# Power.net
KiCad netlist of a schematic drawn in Altium Designer
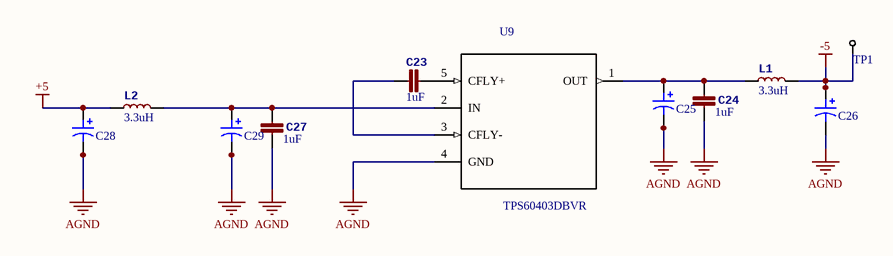
[diagram p0: Power.SchDoc]

(export (version "E")
  (design (tool "Eeschema 10.0.6"))
  (components
    (comp (ref "C23")
      (value "1uF")
      (footprint "_0805")
      (fields (field (name "Comment") "Cap"))
      (libsource (lib "") (part "Cap_1_1"))
    )
    (comp (ref "C24")
      (value "1uF")
      (footprint "_0805")
      (fields (field (name "Comment") "Cap"))
      (libsource (lib "Passives_Integrated_Library") (part "Cap_1"))
    )
    (comp (ref "C25")
      (value "100uF50V")
      (footprint "Cap electrolitic radial 10x20-5")
      (description "Cap electrolitic radial")
      (fields (field (name "DESIGNER") "Abbas Basereh"))
      (libsource (lib "Passives_Integrated_Library") (part "Cap ELECTROLITIC TOTAL SIZE"))
    )
    (comp (ref "C26")
      (value "100uF50V")
      (footprint "Cap electrolitic radial 10x20-5")
      (description "Cap electrolitic radial")
      (fields (field (name "DESIGNER") "Abbas Basereh"))
      (libsource (lib "Passives_Integrated_Library") (part "Cap ELECTROLITIC TOTAL SIZE"))
    )
    (comp (ref "C27")
      (value "1uF")
      (footprint "_0805")
      (fields (field (name "Comment") "Cap"))
      (libsource (lib "Passives_Integrated_Library") (part "Cap_1"))
    )
    (comp (ref "C28")
      (value "100uF50V")
      (footprint "Cap electrolitic radial 10x20-5")
      (description "Cap electrolitic radial")
      (fields (field (name "DESIGNER") "Abbas Basereh"))
      (libsource (lib "Passives_Integrated_Library") (part "Cap ELECTROLITIC TOTAL SIZE"))
    )
    (comp (ref "C29")
      (value "100uF50V")
      (footprint "Cap electrolitic radial 10x20-5")
      (description "Cap electrolitic radial")
      (fields (field (name "DESIGNER") "Abbas Basereh"))
      (libsource (lib "Passives_Integrated_Library") (part "Cap ELECTROLITIC TOTAL SIZE"))
    )
    (comp (ref "L1")
      (value "3.3uH")
      (footprint "_INDUCTOR-SMD-6.0mm")
      (fields (field (name "Comment") "Inductor"))
      (libsource (lib "Passives_Integrated_Library") (part "Inductor"))
    )
    (comp (ref "L2")
      (value "3.3uH")
      (footprint "_INDUCTOR-SMD-6.0mm")
      (fields (field (name "Comment") "Inductor"))
      (libsource (lib "Passives_Integrated_Library") (part "Inductor"))
    )
    (comp (ref "TP1")
      (value "Test Point")
      (footprint "Test Point")
      (libsource (lib "General 2") (part "Test Point"))
    )
    (comp (ref "U9")
      (value "TPS60403DBVR")
      (footprint "*SOT95P280X145-5N")
      (description "60mA Charge Pump Voltage Inverter with Fixed 250kHz Operation 5-SOT-23 -40 to 85")
      (fields (field (name "MF") "Texas Instruments"))
      (libsource (lib "Regulators_Integrated_Library") (part "TPS60403DBVR"))
    )
  )
  (nets
    (net (code "1") (name "+5") (class "Default")
      (node (ref "C28") (pin "1") (pinfunction "1_1") (pintype "passive"))
      (node (ref "L2") (pin "1") (pinfunction "1_1") (pintype "passive"))
    )
    (net (code "2") (name "-5") (class "Default")
      (node (ref "C26") (pin "1") (pinfunction "1_1") (pintype "passive"))
      (node (ref "L1") (pin "2") (pinfunction "2_2") (pintype "passive"))
      (node (ref "TP1") (pin "1") (pinfunction "T_1") (pintype "passive"))
    )
    (net (code "3") (name "AGND") (class "Default")
      (node (ref "C24") (pin "2") (pinfunction "2_2") (pintype "passive"))
      (node (ref "C25") (pin "2") (pinfunction "2_2") (pintype "passive"))
      (node (ref "C26") (pin "2") (pinfunction "2_2") (pintype "passive"))
      (node (ref "C27") (pin "2") (pinfunction "2_2") (pintype "passive"))
      (node (ref "C28") (pin "2") (pinfunction "2_2") (pintype "passive"))
      (node (ref "C29") (pin "2") (pinfunction "2_2") (pintype "passive"))
      (node (ref "U9") (pin "4") (pinfunction "GND_4") (pintype "passive"))
    )
    (net (code "4") (name "Net-(U9-CFLY+)") (class "Default")
      (node (ref "C23") (pin "2") (pinfunction "2_2") (pintype "passive"))
      (node (ref "U9") (pin "5") (pinfunction "CFLY+_5") (pintype "input"))
    )
    (net (code "5") (name "Net-(U9-CFLY-)") (class "Default")
      (node (ref "C23") (pin "1") (pinfunction "1_1") (pintype "passive"))
      (node (ref "U9") (pin "3") (pinfunction "CFLY-_3") (pintype "input"))
    )
    (net (code "6") (name "Net-(U9-IN)") (class "Default")
      (node (ref "C27") (pin "1") (pinfunction "1_1") (pintype "passive"))
      (node (ref "C29") (pin "1") (pinfunction "1_1") (pintype "passive"))
      (node (ref "L2") (pin "2") (pinfunction "2_2") (pintype "passive"))
      (node (ref "U9") (pin "2") (pinfunction "IN_2") (pintype "power_in"))
    )
    (net (code "7") (name "Net-(U9-OUT)") (class "Default")
      (node (ref "C24") (pin "1") (pinfunction "1_1") (pintype "passive"))
      (node (ref "C25") (pin "1") (pinfunction "1_1") (pintype "passive"))
      (node (ref "L1") (pin "1") (pinfunction "1_1") (pintype "passive"))
      (node (ref "U9") (pin "1") (pinfunction "OUT_1") (pintype "output"))
    )
  )
)
